# tempSensorAAABat.net
KiCad netlist of a schematic drawn in EAGLE
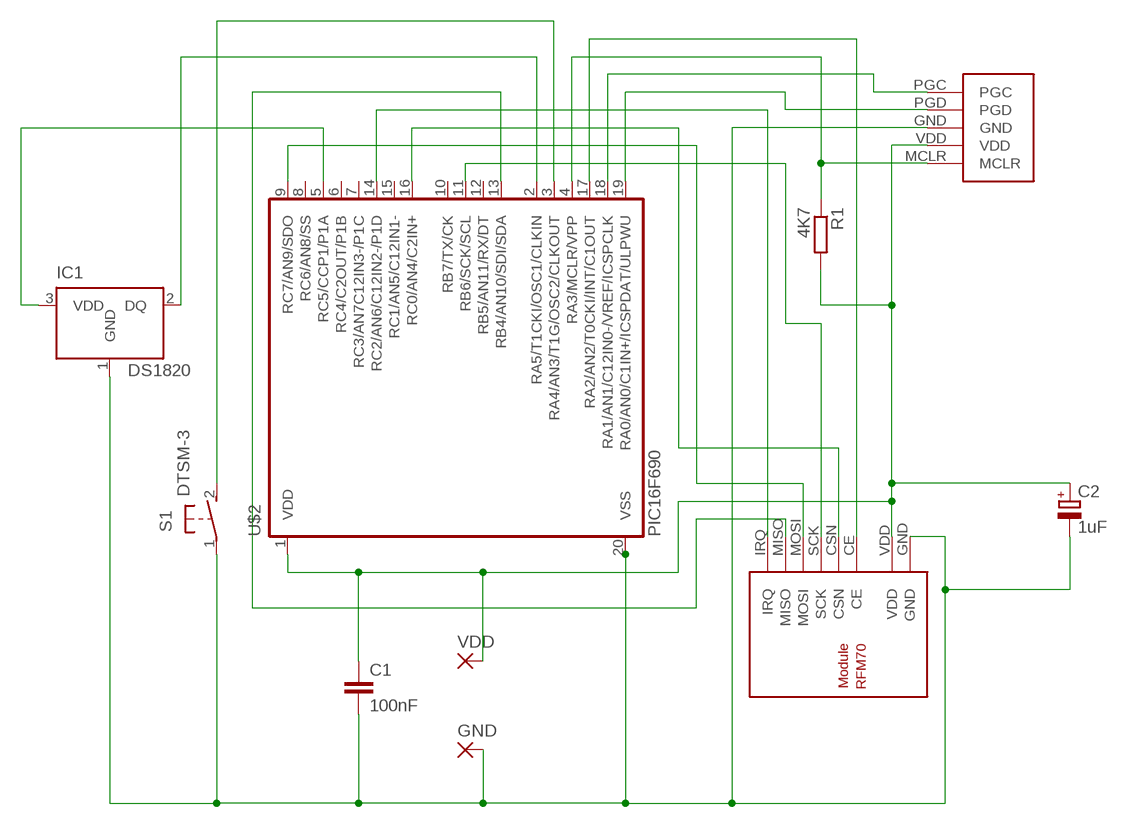
[diagram p0: schematic, sheet 1]

(export (version "E")
  (design (tool "Eeschema 10.0.6"))
  (components
    (comp (ref "C1")
      (value "100nF")
      (footprint "eagle-import:C2012")
      (libsource (lib "eagle-import") (part "C-EUC2012"))
    )
    (comp (ref "C2")
      (value "1uF")
      (footprint "eagle-import:SMC_A")
      (libsource (lib "eagle-import") (part "CPOL-EUSMCA"))
    )
    (comp (ref "GND")
      (value "SMD5")
      (footprint "eagle-import:SMD2,54-5,08")
      (libsource (lib "eagle-import") (part "SMD5"))
    )
    (comp (ref "IC1")
      (value "DS1820")
      (footprint "eagle-import:TO-92")
      (libsource (lib "eagle-import") (part "DS1820"))
    )
    (comp (ref "R1")
      (value "4K7")
      (footprint "eagle-import:R1206W")
      (libsource (lib "eagle-import") (part "R-EU_R1206W"))
    )
    (comp (ref "S1")
      (value "DTSM-3")
      (footprint "eagle-import:DTSM-3")
      (libsource (lib "eagle-import") (part "DTSM-3"))
    )
    (comp (ref "U$1")
      (value "RFM70")
      (footprint "eagle-import:RFM70")
      (libsource (lib "eagle-import") (part "RFM70"))
    )
    (comp (ref "U$2")
      (value "PIC16F690")
      (footprint "eagle-import:SSOP20")
      (libsource (lib "eagle-import") (part "PIC16F690"))
    )
    (comp (ref "U$3")
      (value "PROGRAMMINGHEADERDIP")
      (footprint "eagle-import:PROGHEADER")
      (libsource (lib "eagle-import") (part "PROGRAMMINGHEADERDIP"))
    )
    (comp (ref "VDD")
      (value "SMD5")
      (footprint "eagle-import:SMD2,54-5,08")
      (libsource (lib "eagle-import") (part "SMD5"))
    )
  )
  (nets
    (net (code "1") (name "Net-(GND-P)") (class "Default")
      (node (ref "C1") (pin "2") (pinfunction "2_2") (pintype "passive"))
      (node (ref "C2") (pin "-") (pinfunction "-_-") (pintype "passive"))
      (node (ref "GND") (pin "1") (pinfunction "P_1") (pintype "passive"))
      (node (ref "IC1") (pin "1") (pinfunction "GND_1") (pintype "power_in"))
      (node (ref "S1") (pin "1") (pinfunction "1_1") (pintype "passive"))
      (node (ref "U$1") (pin "GND") (pinfunction "GND_GND") (pintype "power_in"))
      (node (ref "U$2") (pin "20") (pinfunction "VSS_20") (pintype "power_in"))
      (node (ref "U$3") (pin "GND") (pinfunction "GND_GND") (pintype "power_in"))
    )
    (net (code "2") (name "Net-(IC1-DQ)") (class "Default")
      (node (ref "IC1") (pin "2") (pinfunction "DQ_2") (pintype "output"))
      (node (ref "U$2") (pin "2") (pinfunction "RA5/T1CKI/OSC1/CLKIN_2") (pintype "bidirectional"))
    )
    (net (code "3") (name "Net-(IC1-VDD)") (class "Default")
      (node (ref "IC1") (pin "3") (pinfunction "VDD_3") (pintype "input"))
      (node (ref "U$2") (pin "5") (pinfunction "RC5/CCP1/P1A_5") (pintype "bidirectional"))
    )
    (net (code "4") (name "Net-(U$2-RA0{slash}AN0{slash}C1IN+{slash}ICSPDAT{slash}ULPWU)") (class "Default")
      (node (ref "U$2") (pin "19") (pinfunction "RA0/AN0/C1IN+/ICSPDAT/ULPWU_19") (pintype "bidirectional"))
      (node (ref "U$3") (pin "PGD") (pinfunction "PGD_PGD") (pintype "bidirectional"))
    )
    (net (code "5") (name "Net-(U$2-RA1{slash}AN1{slash}C12IN0-{slash}VREF{slash}ICSPCLK)") (class "Default")
      (node (ref "U$2") (pin "18") (pinfunction "RA1/AN1/C12IN0-/VREF/ICSPCLK_18") (pintype "bidirectional"))
      (node (ref "U$3") (pin "PGC") (pinfunction "PGC_PGC") (pintype "bidirectional"))
    )
    (net (code "6") (name "Net-(U$2-RA2{slash}AN2{slash}T0CKI{slash}INT{slash}C1OUT)") (class "Default")
      (node (ref "U$1") (pin "CE") (pinfunction "CE_CE") (pintype "bidirectional"))
      (node (ref "U$2") (pin "17") (pinfunction "RA2/AN2/T0CKI/INT/C1OUT_17") (pintype "bidirectional"))
    )
    (net (code "7") (name "Net-(U$2-RA3{slash}MCLR{slash}VPP)") (class "Default")
      (node (ref "R1") (pin "1") (pinfunction "1_1") (pintype "passive"))
      (node (ref "U$2") (pin "4") (pinfunction "RA3/MCLR/VPP_4") (pintype "bidirectional"))
      (node (ref "U$3") (pin "MCLR") (pinfunction "MCLR_MCLR") (pintype "output"))
    )
    (net (code "8") (name "Net-(U$2-RA4{slash}AN3{slash}T1G{slash}OSC2{slash}CLKOUT)") (class "Default")
      (node (ref "S1") (pin "2") (pinfunction "2_2") (pintype "passive"))
      (node (ref "U$2") (pin "3") (pinfunction "RA4/AN3/T1G/OSC2/CLKOUT_3") (pintype "bidirectional"))
    )
    (net (code "9") (name "Net-(U$2-RB4{slash}AN10{slash}SDI{slash}SDA)") (class "Default")
      (node (ref "U$1") (pin "MISO") (pinfunction "MISO_MISO") (pintype "bidirectional"))
      (node (ref "U$2") (pin "13") (pinfunction "RB4/AN10/SDI/SDA_13") (pintype "bidirectional"))
    )
    (net (code "10") (name "Net-(U$2-RB6{slash}SCK{slash}SCL)") (class "Default")
      (node (ref "U$1") (pin "SCK") (pinfunction "SCK_SCK") (pintype "bidirectional"))
      (node (ref "U$2") (pin "11") (pinfunction "RB6/SCK/SCL_11") (pintype "bidirectional"))
    )
    (net (code "11") (name "Net-(U$2-RC0{slash}AN4{slash}C2IN+)") (class "Default")
      (node (ref "U$1") (pin "CSN") (pinfunction "CSN_CSN") (pintype "bidirectional"))
      (node (ref "U$2") (pin "16") (pinfunction "RC0/AN4/C2IN+_16") (pintype "bidirectional"))
    )
    (net (code "12") (name "Net-(U$2-RC2{slash}AN6{slash}C12IN2-{slash}P1D)") (class "Default")
      (node (ref "U$1") (pin "IRQ") (pinfunction "IRQ_IRQ") (pintype "bidirectional"))
      (node (ref "U$2") (pin "14") (pinfunction "RC2/AN6/C12IN2-/P1D_14") (pintype "bidirectional"))
    )
    (net (code "13") (name "Net-(U$2-RC7{slash}AN9{slash}SDO)") (class "Default")
      (node (ref "U$1") (pin "MOSI") (pinfunction "MOSI_MOSI") (pintype "bidirectional"))
      (node (ref "U$2") (pin "9") (pinfunction "RC7/AN9/SDO_9") (pintype "bidirectional"))
    )
    (net (code "14") (name "Net-(U$2-VDD)") (class "Default")
      (node (ref "C1") (pin "1") (pinfunction "1_1") (pintype "passive"))
      (node (ref "C2") (pin "+") (pinfunction "+_+") (pintype "passive"))
      (node (ref "R1") (pin "2") (pinfunction "2_2") (pintype "passive"))
      (node (ref "U$1") (pin "VDD") (pinfunction "VDD_VDD") (pintype "power_in"))
      (node (ref "U$2") (pin "1") (pinfunction "VDD_1") (pintype "power_in"))
      (node (ref "U$3") (pin "VDD") (pinfunction "VDD_VDD") (pintype "power_in"))
      (node (ref "VDD") (pin "1") (pinfunction "P_1") (pintype "passive"))
    )
    (net (code "15") (name "unconnected-(U$2-RB5{slash}AN11{slash}RX{slash}DT-Pad12)") (class "Default")
      (node (ref "U$2") (pin "12") (pinfunction "RB5/AN11/RX/DT_12") (pintype "bidirectional"))
    )
    (net (code "16") (name "unconnected-(U$2-RB7{slash}TX{slash}CK-Pad10)") (class "Default")
      (node (ref "U$2") (pin "10") (pinfunction "RB7/TX/CK_10") (pintype "bidirectional"))
    )
    (net (code "17") (name "unconnected-(U$2-RC1{slash}AN5{slash}C12IN1--Pad15)") (class "Default")
      (node (ref "U$2") (pin "15") (pinfunction "RC1/AN5/C12IN1-_15") (pintype "bidirectional"))
    )
    (net (code "18") (name "unconnected-(U$2-RC3{slash}AN7C12IN3-{slash}P1C-Pad7)") (class "Default")
      (node (ref "U$2") (pin "7") (pinfunction "RC3/AN7C12IN3-/P1C_7") (pintype "bidirectional"))
    )
    (net (code "19") (name "unconnected-(U$2-RC4{slash}C2OUT{slash}P1B-Pad6)") (class "Default")
      (node (ref "U$2") (pin "6") (pinfunction "RC4/C2OUT/P1B_6") (pintype "bidirectional"))
    )
    (net (code "20") (name "unconnected-(U$2-RC6{slash}AN8{slash}SS-Pad8)") (class "Default")
      (node (ref "U$2") (pin "8") (pinfunction "RC6/AN8/SS_8") (pintype "bidirectional"))
    )
  )
)
